# Esquematico.net
KiCad netlist of a schematic drawn in EAGLE
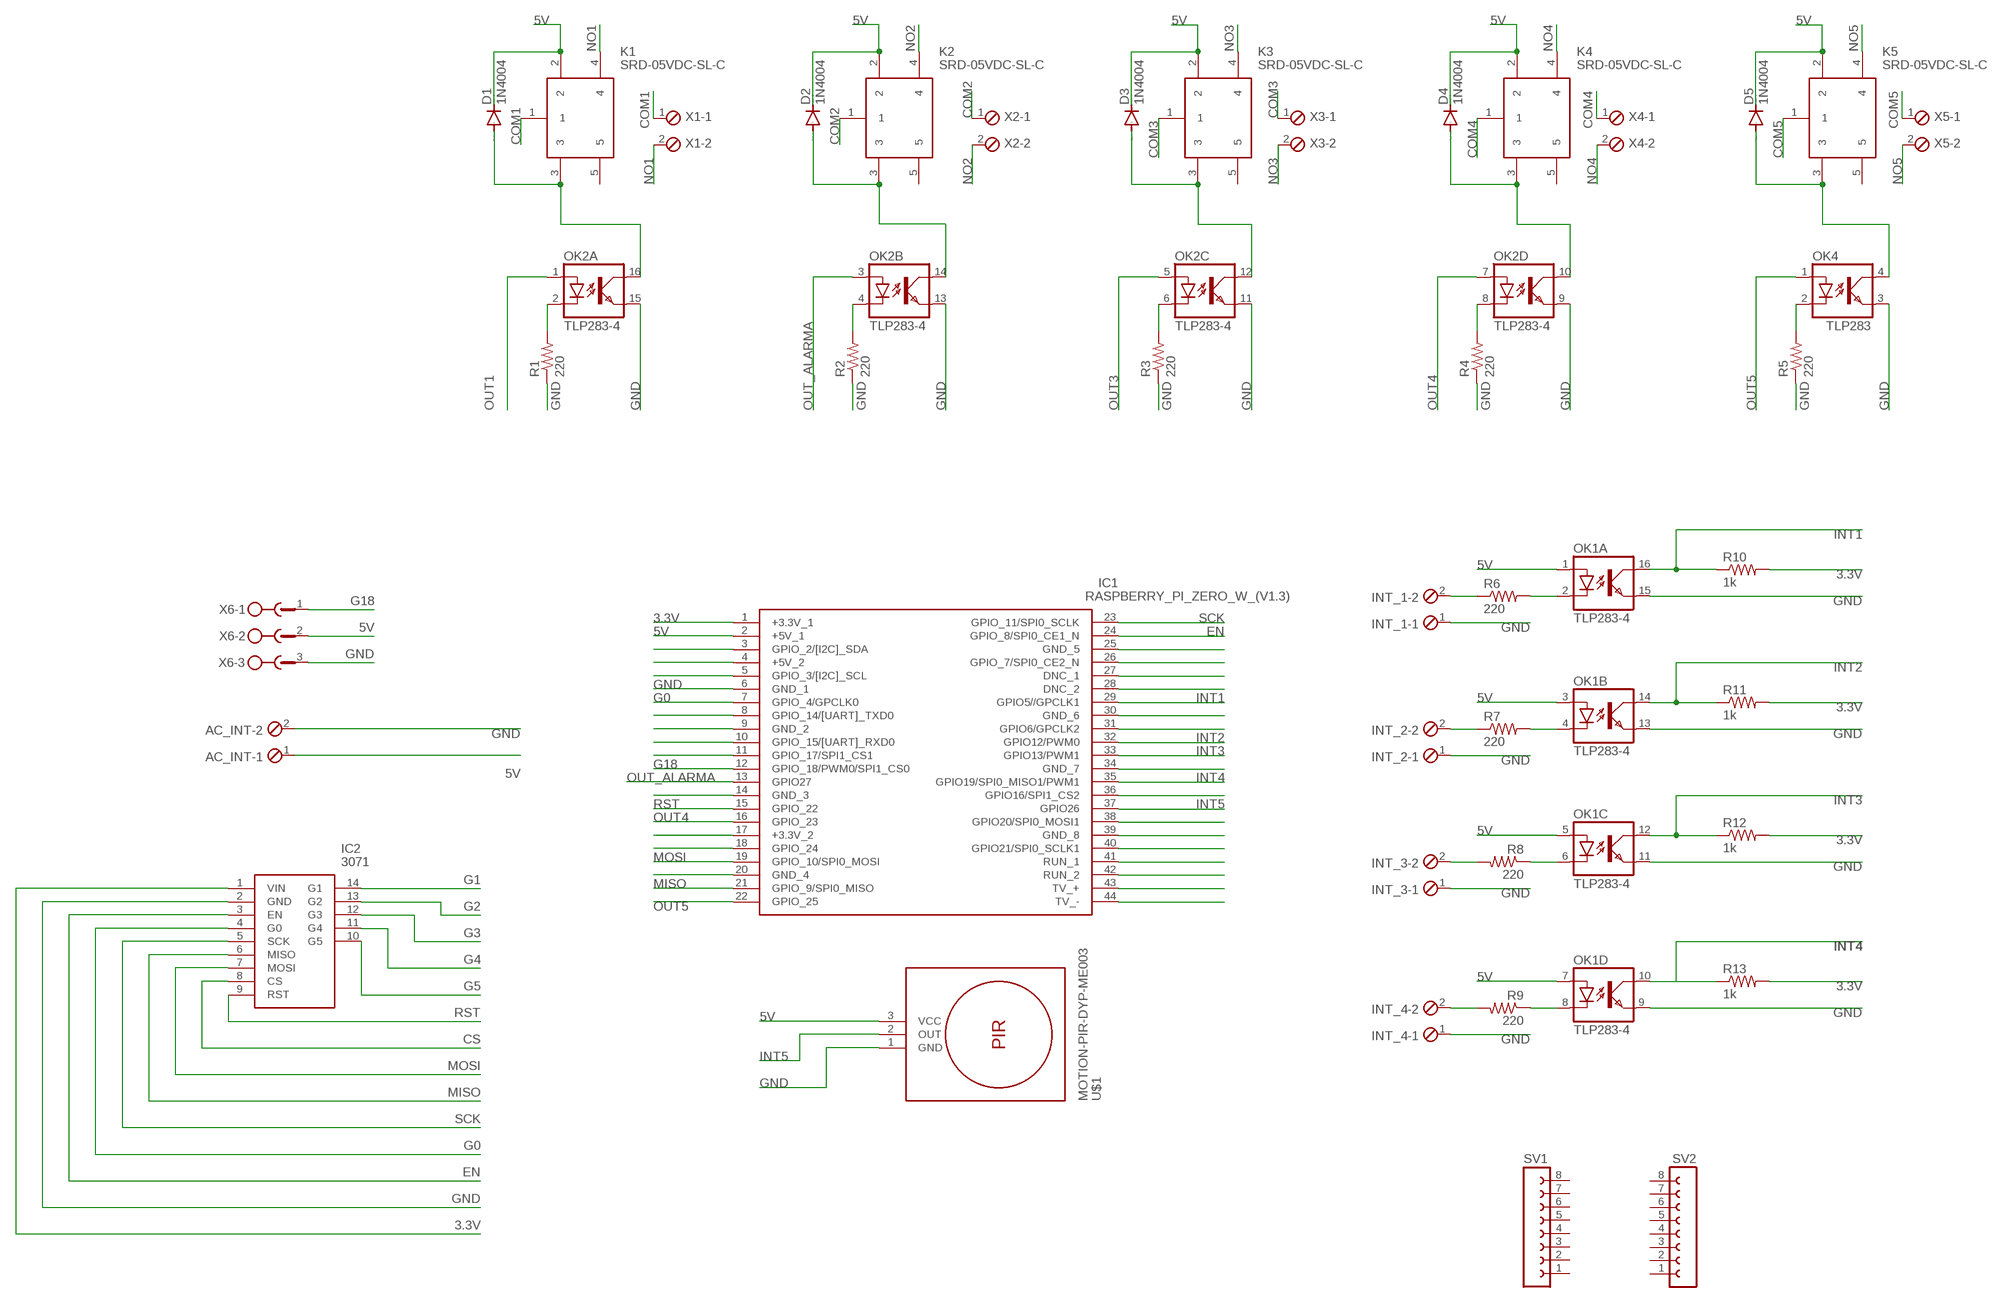
[diagram p0: schematic, sheet 1]

(export (version "E")
  (design (tool "Eeschema 10.0.6"))
  (components
    (comp (ref "AC_INT")
      (value "MPT2")
      (footprint "eagle-import:2POL254")
      (libsource (lib "eagle-import") (part "MPT2"))
    )
    (comp (ref "D1")
      (value "1N4004")
      (footprint "eagle-import:DO41-10")
      (libsource (lib "eagle-import") (part "1N4004"))
    )
    (comp (ref "D2")
      (value "1N4004")
      (footprint "eagle-import:DO41-10")
      (libsource (lib "eagle-import") (part "1N4004"))
    )
    (comp (ref "D3")
      (value "1N4004")
      (footprint "eagle-import:DO41-10")
      (libsource (lib "eagle-import") (part "1N4004"))
    )
    (comp (ref "D4")
      (value "1N4004")
      (footprint "eagle-import:DO41-10")
      (libsource (lib "eagle-import") (part "1N4004"))
    )
    (comp (ref "D5")
      (value "1N4004")
      (footprint "eagle-import:DO41-10")
      (libsource (lib "eagle-import") (part "1N4004"))
    )
    (comp (ref "IC1")
      (value "RASPBERRY_PI_ZERO_W_(V1.3)")
      (footprint "eagle-import:RASPBERRYPIZEROWV13")
      (fields (field (name "MANUFACTURER_PART_NUMBER") "Raspberry Pi Zero W (v1.3)"))
      (libsource (lib "eagle-import") (part "RASPBERRY_PI_ZERO_W_(V1.3)"))
    )
    (comp (ref "IC2")
      (value "3071")
      (footprint "eagle-import:3071")
      (fields (field (name "MOUSER_PART_NUMBER") "485-3071"))
      (libsource (lib "eagle-import") (part "3071"))
    )
    (comp (ref "INT_1")
      (value "MPT2")
      (footprint "eagle-import:2POL254")
      (libsource (lib "eagle-import") (part "MPT2"))
    )
    (comp (ref "INT_2")
      (value "MPT2")
      (footprint "eagle-import:2POL254")
      (libsource (lib "eagle-import") (part "MPT2"))
    )
    (comp (ref "INT_3")
      (value "MPT2")
      (footprint "eagle-import:2POL254")
      (libsource (lib "eagle-import") (part "MPT2"))
    )
    (comp (ref "INT_4")
      (value "MPT2")
      (footprint "eagle-import:2POL254")
      (libsource (lib "eagle-import") (part "MPT2"))
    )
    (comp (ref "K1")
      (value "SRD-05VDC-SL-C")
      (footprint "eagle-import:SRD")
      (libsource (lib "eagle-import") (part "SRD-05VDC-SL-C"))
    )
    (comp (ref "K2")
      (value "SRD-05VDC-SL-C")
      (footprint "eagle-import:SRD")
      (libsource (lib "eagle-import") (part "SRD-05VDC-SL-C"))
    )
    (comp (ref "K3")
      (value "SRD-05VDC-SL-C")
      (footprint "eagle-import:SRD")
      (libsource (lib "eagle-import") (part "SRD-05VDC-SL-C"))
    )
    (comp (ref "K4")
      (value "SRD-05VDC-SL-C")
      (footprint "eagle-import:SRD")
      (libsource (lib "eagle-import") (part "SRD-05VDC-SL-C"))
    )
    (comp (ref "K5")
      (value "SRD-05VDC-SL-C")
      (footprint "eagle-import:SRD")
      (libsource (lib "eagle-import") (part "SRD-05VDC-SL-C"))
    )
    (comp (ref "OK1")
      (value "TLP283-4")
      (footprint "eagle-import:MINI-FLAT-16")
      (libsource (lib "eagle-import") (part "TLP283-4"))
    )
    (comp (ref "OK2")
      (value "TLP283-4")
      (footprint "eagle-import:MINI-FLAT-16")
      (libsource (lib "eagle-import") (part "TLP283-4"))
    )
    (comp (ref "OK4")
      (value "TLP283")
      (footprint "eagle-import:MINI-FLAT-4")
      (libsource (lib "eagle-import") (part "TLP283"))
    )
    (comp (ref "R1")
      (value "220")
      (footprint "eagle-import:R0402")
      (libsource (lib "eagle-import") (part "R-US_R0402"))
    )
    (comp (ref "R2")
      (value "220")
      (footprint "eagle-import:R0402")
      (libsource (lib "eagle-import") (part "R-US_R0402"))
    )
    (comp (ref "R3")
      (value "220")
      (footprint "eagle-import:R0402")
      (libsource (lib "eagle-import") (part "R-US_R0402"))
    )
    (comp (ref "R4")
      (value "220")
      (footprint "eagle-import:R0402")
      (libsource (lib "eagle-import") (part "R-US_R0402"))
    )
    (comp (ref "R5")
      (value "220")
      (footprint "eagle-import:R0402")
      (libsource (lib "eagle-import") (part "R-US_R0402"))
    )
    (comp (ref "R6")
      (value "220")
      (footprint "eagle-import:R0402")
      (libsource (lib "eagle-import") (part "R-US_R0402"))
    )
    (comp (ref "R7")
      (value "220")
      (footprint "eagle-import:R0402")
      (libsource (lib "eagle-import") (part "R-US_R0402"))
    )
    (comp (ref "R8")
      (value "220")
      (footprint "eagle-import:R0402")
      (libsource (lib "eagle-import") (part "R-US_R0402"))
    )
    (comp (ref "R9")
      (value "220")
      (footprint "eagle-import:R0402")
      (libsource (lib "eagle-import") (part "R-US_R0402"))
    )
    (comp (ref "R10")
      (value "1k")
      (footprint "eagle-import:R0402")
      (libsource (lib "eagle-import") (part "R-US_R0402"))
    )
    (comp (ref "R11")
      (value "1k")
      (footprint "eagle-import:R0402")
      (libsource (lib "eagle-import") (part "R-US_R0402"))
    )
    (comp (ref "R12")
      (value "1k")
      (footprint "eagle-import:R0402")
      (libsource (lib "eagle-import") (part "R-US_R0402"))
    )
    (comp (ref "R13")
      (value "1k")
      (footprint "eagle-import:R0402")
      (libsource (lib "eagle-import") (part "R-US_R0402"))
    )
    (comp (ref "SV1")
      (value "FE08W")
      (footprint "eagle-import:FE08W")
      (libsource (lib "eagle-import") (part "FE08W"))
    )
    (comp (ref "SV2")
      (value "FE08W")
      (footprint "eagle-import:FE08W")
      (libsource (lib "eagle-import") (part "FE08W"))
    )
    (comp (ref "U$1")
      (value "MOTION-PIR-DYP-ME003")
      (footprint "eagle-import:MOTION-PIR-DYP-ME003")
      (libsource (lib "eagle-import") (part "MOTION-PIR-DYP-ME003"))
    )
    (comp (ref "X1")
      (value "MPT2")
      (footprint "eagle-import:2POL254")
      (libsource (lib "eagle-import") (part "MPT2"))
    )
    (comp (ref "X2")
      (value "MPT2")
      (footprint "eagle-import:2POL254")
      (libsource (lib "eagle-import") (part "MPT2"))
    )
    (comp (ref "X3")
      (value "MPT2")
      (footprint "eagle-import:2POL254")
      (libsource (lib "eagle-import") (part "MPT2"))
    )
    (comp (ref "X4")
      (value "MPT2")
      (footprint "eagle-import:2POL254")
      (libsource (lib "eagle-import") (part "MPT2"))
    )
    (comp (ref "X5")
      (value "MPT2")
      (footprint "eagle-import:2POL254")
      (libsource (lib "eagle-import") (part "MPT2"))
    )
    (comp (ref "X6")
      (value "W232-3")
      (footprint "eagle-import:W232-3")
      (libsource (lib "eagle-import") (part "W232-3"))
    )
  )
  (nets
    (net (code "1") (name "/3.3V") (class "Default")
      (node (ref "IC1") (pin "1") (pinfunction "+3.3V_1_1") (pintype "bidirectional"))
      (node (ref "IC2") (pin "1") (pinfunction "VIN_1") (pintype "bidirectional"))
      (node (ref "R10") (pin "2") (pinfunction "2_2") (pintype "passive"))
      (node (ref "R11") (pin "2") (pinfunction "2_2") (pintype "passive"))
      (node (ref "R12") (pin "2") (pinfunction "2_2") (pintype "passive"))
      (node (ref "R13") (pin "2") (pinfunction "2_2") (pintype "passive"))
    )
    (net (code "2") (name "/5V") (class "Default")
      (node (ref "AC_INT") (pin "1") (pinfunction "1_1") (pintype "passive"))
      (node (ref "D1") (pin "C") (pinfunction "C_C") (pintype "passive"))
      (node (ref "D2") (pin "C") (pinfunction "C_C") (pintype "passive"))
      (node (ref "D3") (pin "C") (pinfunction "C_C") (pintype "passive"))
      (node (ref "D4") (pin "C") (pinfunction "C_C") (pintype "passive"))
      (node (ref "D5") (pin "C") (pinfunction "C_C") (pintype "passive"))
      (node (ref "IC1") (pin "2") (pinfunction "+5V_1_2") (pintype "bidirectional"))
      (node (ref "K1") (pin "2") (pinfunction "2_2") (pintype "bidirectional"))
      (node (ref "K2") (pin "2") (pinfunction "2_2") (pintype "bidirectional"))
      (node (ref "K3") (pin "2") (pinfunction "2_2") (pintype "bidirectional"))
      (node (ref "K4") (pin "2") (pinfunction "2_2") (pintype "bidirectional"))
      (node (ref "K5") (pin "2") (pinfunction "2_2") (pintype "bidirectional"))
      (node (ref "OK1") (pin "1") (pinfunction "A_1") (pintype "passive"))
      (node (ref "OK1") (pin "3") (pinfunction "A_3") (pintype "passive"))
      (node (ref "OK1") (pin "5") (pinfunction "A_5") (pintype "passive"))
      (node (ref "OK1") (pin "7") (pinfunction "A_7") (pintype "passive"))
      (node (ref "U$1") (pin "3") (pinfunction "VCC_3") (pintype "power_in"))
      (node (ref "X6") (pin "2") (pinfunction "SK_2") (pintype "passive"))
    )
    (net (code "3") (name "/COM1") (class "Default")
      (node (ref "K1") (pin "1") (pinfunction "1_1") (pintype "bidirectional"))
      (node (ref "X1") (pin "1") (pinfunction "1_1") (pintype "passive"))
    )
    (net (code "4") (name "/COM2") (class "Default")
      (node (ref "K2") (pin "1") (pinfunction "1_1") (pintype "bidirectional"))
      (node (ref "X2") (pin "1") (pinfunction "1_1") (pintype "passive"))
    )
    (net (code "5") (name "/COM3") (class "Default")
      (node (ref "K3") (pin "1") (pinfunction "1_1") (pintype "bidirectional"))
      (node (ref "X3") (pin "1") (pinfunction "1_1") (pintype "passive"))
    )
    (net (code "6") (name "/COM4") (class "Default")
      (node (ref "K4") (pin "1") (pinfunction "1_1") (pintype "bidirectional"))
      (node (ref "X4") (pin "1") (pinfunction "1_1") (pintype "passive"))
    )
    (net (code "7") (name "/COM5") (class "Default")
      (node (ref "K5") (pin "1") (pinfunction "1_1") (pintype "bidirectional"))
      (node (ref "X5") (pin "1") (pinfunction "1_1") (pintype "passive"))
    )
    (net (code "8") (name "/CS") (class "Default")
      (node (ref "IC2") (pin "8") (pinfunction "CS_8") (pintype "bidirectional"))
    )
    (net (code "9") (name "/EN") (class "Default")
      (node (ref "IC1") (pin "24") (pinfunction "GPIO_8/SPI0_CE1_N_24") (pintype "bidirectional"))
      (node (ref "IC2") (pin "3") (pinfunction "EN_3") (pintype "bidirectional"))
    )
    (net (code "10") (name "/G0") (class "Default")
      (node (ref "IC1") (pin "7") (pinfunction "GPIO_4/GPCLK0_7") (pintype "bidirectional"))
      (node (ref "IC2") (pin "4") (pinfunction "G0_4") (pintype "bidirectional"))
    )
    (net (code "11") (name "/G1") (class "Default")
      (node (ref "IC2") (pin "14") (pinfunction "G1_14") (pintype "bidirectional"))
    )
    (net (code "12") (name "/G2") (class "Default")
      (node (ref "IC2") (pin "13") (pinfunction "G2_13") (pintype "bidirectional"))
    )
    (net (code "13") (name "/G3") (class "Default")
      (node (ref "IC2") (pin "12") (pinfunction "G3_12") (pintype "bidirectional"))
    )
    (net (code "14") (name "/G4") (class "Default")
      (node (ref "IC2") (pin "11") (pinfunction "G4_11") (pintype "bidirectional"))
    )
    (net (code "15") (name "/G5") (class "Default")
      (node (ref "IC2") (pin "10") (pinfunction "G5_10") (pintype "bidirectional"))
    )
    (net (code "16") (name "/G18") (class "Default")
      (node (ref "IC1") (pin "12") (pinfunction "GPIO_18/PWM0/SPI1_CS0_12") (pintype "bidirectional"))
      (node (ref "X6") (pin "1") (pinfunction "SK_1") (pintype "passive"))
    )
    (net (code "17") (name "/GND") (class "Default")
      (node (ref "AC_INT") (pin "2") (pinfunction "1_2") (pintype "passive"))
      (node (ref "IC1") (pin "6") (pinfunction "GND_1_6") (pintype "bidirectional"))
      (node (ref "IC2") (pin "2") (pinfunction "GND_2") (pintype "bidirectional"))
      (node (ref "INT_1") (pin "1") (pinfunction "1_1") (pintype "passive"))
      (node (ref "INT_2") (pin "1") (pinfunction "1_1") (pintype "passive"))
      (node (ref "INT_3") (pin "1") (pinfunction "1_1") (pintype "passive"))
      (node (ref "INT_4") (pin "1") (pinfunction "1_1") (pintype "passive"))
      (node (ref "OK1") (pin "11") (pinfunction "EMIT_11") (pintype "passive"))
      (node (ref "OK1") (pin "13") (pinfunction "EMIT_13") (pintype "passive"))
      (node (ref "OK1") (pin "15") (pinfunction "EMIT_15") (pintype "passive"))
      (node (ref "OK1") (pin "9") (pinfunction "EMIT_9") (pintype "passive"))
      (node (ref "OK2") (pin "11") (pinfunction "EMIT_11") (pintype "passive"))
      (node (ref "OK2") (pin "13") (pinfunction "EMIT_13") (pintype "passive"))
      (node (ref "OK2") (pin "15") (pinfunction "EMIT_15") (pintype "passive"))
      (node (ref "OK2") (pin "9") (pinfunction "EMIT_9") (pintype "passive"))
      (node (ref "OK4") (pin "3") (pinfunction "EMIT_3") (pintype "passive"))
      (node (ref "R1") (pin "1") (pinfunction "1_1") (pintype "passive"))
      (node (ref "R2") (pin "1") (pinfunction "1_1") (pintype "passive"))
      (node (ref "R3") (pin "1") (pinfunction "1_1") (pintype "passive"))
      (node (ref "R4") (pin "1") (pinfunction "1_1") (pintype "passive"))
      (node (ref "R5") (pin "1") (pinfunction "1_1") (pintype "passive"))
      (node (ref "U$1") (pin "1") (pinfunction "GND_1") (pintype "power_in"))
      (node (ref "X6") (pin "3") (pinfunction "SK_3") (pintype "passive"))
    )
    (net (code "18") (name "/INT1") (class "Default")
      (node (ref "IC1") (pin "29") (pinfunction "GPIO5//GPCLK1_29") (pintype "bidirectional"))
      (node (ref "OK1") (pin "16") (pinfunction "COL_16") (pintype "passive"))
      (node (ref "R10") (pin "1") (pinfunction "1_1") (pintype "passive"))
    )
    (net (code "19") (name "/INT2") (class "Default")
      (node (ref "IC1") (pin "32") (pinfunction "GPIO12/PWM0_32") (pintype "bidirectional"))
      (node (ref "OK1") (pin "14") (pinfunction "COL_14") (pintype "passive"))
      (node (ref "R11") (pin "1") (pinfunction "1_1") (pintype "passive"))
    )
    (net (code "20") (name "/INT3") (class "Default")
      (node (ref "IC1") (pin "33") (pinfunction "GPIO13/PWM1_33") (pintype "bidirectional"))
      (node (ref "OK1") (pin "12") (pinfunction "COL_12") (pintype "passive"))
      (node (ref "R12") (pin "1") (pinfunction "1_1") (pintype "passive"))
    )
    (net (code "21") (name "/INT4") (class "Default")
      (node (ref "IC1") (pin "35") (pinfunction "GPIO19/SPI0_MISO1/PWM1_35") (pintype "bidirectional"))
      (node (ref "OK1") (pin "10") (pinfunction "COL_10") (pintype "passive"))
      (node (ref "R13") (pin "1") (pinfunction "1_1") (pintype "passive"))
    )
    (net (code "22") (name "/INT5") (class "Default")
      (node (ref "IC1") (pin "37") (pinfunction "GPIO26_37") (pintype "bidirectional"))
      (node (ref "U$1") (pin "2") (pinfunction "OUT_2") (pintype "output"))
    )
    (net (code "23") (name "/MISO") (class "Default")
      (node (ref "IC1") (pin "21") (pinfunction "GPIO_9/SPI0_MISO_21") (pintype "bidirectional"))
      (node (ref "IC2") (pin "6") (pinfunction "MISO_6") (pintype "bidirectional"))
    )
    (net (code "24") (name "/MOSI") (class "Default")
      (node (ref "IC1") (pin "19") (pinfunction "GPIO_10/SPI0_MOSI_19") (pintype "bidirectional"))
      (node (ref "IC2") (pin "7") (pinfunction "MOSI_7") (pintype "bidirectional"))
    )
    (net (code "25") (name "/NO1") (class "Default")
      (node (ref "K1") (pin "4") (pinfunction "4_4") (pintype "bidirectional"))
      (node (ref "X1") (pin "2") (pinfunction "1_2") (pintype "passive"))
    )
    (net (code "26") (name "/NO2") (class "Default")
      (node (ref "K2") (pin "4") (pinfunction "4_4") (pintype "bidirectional"))
      (node (ref "X2") (pin "2") (pinfunction "1_2") (pintype "passive"))
    )
    (net (code "27") (name "/NO3") (class "Default")
      (node (ref "K3") (pin "4") (pinfunction "4_4") (pintype "bidirectional"))
      (node (ref "X3") (pin "2") (pinfunction "1_2") (pintype "passive"))
    )
    (net (code "28") (name "/NO4") (class "Default")
      (node (ref "K4") (pin "4") (pinfunction "4_4") (pintype "bidirectional"))
      (node (ref "X4") (pin "2") (pinfunction "1_2") (pintype "passive"))
    )
    (net (code "29") (name "/NO5") (class "Default")
      (node (ref "K5") (pin "4") (pinfunction "4_4") (pintype "bidirectional"))
      (node (ref "X5") (pin "2") (pinfunction "1_2") (pintype "passive"))
    )
    (net (code "30") (name "/OUT1") (class "Default")
      (node (ref "OK2") (pin "1") (pinfunction "A_1") (pintype "passive"))
    )
    (net (code "31") (name "/OUT3") (class "Default")
      (node (ref "OK2") (pin "5") (pinfunction "A_5") (pintype "passive"))
    )
    (net (code "32") (name "/OUT4") (class "Default")
      (node (ref "IC1") (pin "16") (pinfunction "GPIO_23_16") (pintype "bidirectional"))
      (node (ref "OK2") (pin "7") (pinfunction "A_7") (pintype "passive"))
    )
    (net (code "33") (name "/OUT5") (class "Default")
      (node (ref "IC1") (pin "22") (pinfunction "GPIO_25_22") (pintype "bidirectional"))
      (node (ref "OK4") (pin "1") (pinfunction "A_1") (pintype "passive"))
    )
    (net (code "34") (name "/OUT_ALARMA") (class "Default")
      (node (ref "IC1") (pin "13") (pinfunction "GPIO27_13") (pintype "bidirectional"))
      (node (ref "OK2") (pin "3") (pinfunction "A_3") (pintype "passive"))
    )
    (net (code "35") (name "/RST") (class "Default")
      (node (ref "IC1") (pin "15") (pinfunction "GPIO_22_15") (pintype "bidirectional"))
      (node (ref "IC2") (pin "9") (pinfunction "RST_9") (pintype "bidirectional"))
    )
    (net (code "36") (name "/SCK") (class "Default")
      (node (ref "IC1") (pin "23") (pinfunction "GPIO_11/SPI0_SCLK_23") (pintype "bidirectional"))
      (node (ref "IC2") (pin "5") (pinfunction "SCK_5") (pintype "bidirectional"))
    )
    (net (code "37") (name "Net-(INT_1B-1)") (class "Default")
      (node (ref "INT_1") (pin "2") (pinfunction "1_2") (pintype "passive"))
      (node (ref "R6") (pin "1") (pinfunction "1_1") (pintype "passive"))
    )
    (net (code "38") (name "Net-(INT_2B-1)") (class "Default")
      (node (ref "INT_2") (pin "2") (pinfunction "1_2") (pintype "passive"))
      (node (ref "R7") (pin "1") (pinfunction "1_1") (pintype "passive"))
    )
    (net (code "39") (name "Net-(INT_3B-1)") (class "Default")
      (node (ref "INT_3") (pin "2") (pinfunction "1_2") (pintype "passive"))
      (node (ref "R8") (pin "2") (pinfunction "2_2") (pintype "passive"))
    )
    (net (code "40") (name "Net-(INT_4B-1)") (class "Default")
      (node (ref "INT_4") (pin "2") (pinfunction "1_2") (pintype "passive"))
      (node (ref "R9") (pin "2") (pinfunction "2_2") (pintype "passive"))
    )
    (net (code "41") (name "Net-(OK1A-C)") (class "Default")
      (node (ref "OK1") (pin "2") (pinfunction "C_2") (pintype "passive"))
      (node (ref "R6") (pin "2") (pinfunction "2_2") (pintype "passive"))
    )
    (net (code "42") (name "Net-(OK1B-C)") (class "Default")
      (node (ref "OK1") (pin "4") (pinfunction "C_4") (pintype "passive"))
      (node (ref "R7") (pin "2") (pinfunction "2_2") (pintype "passive"))
    )
    (net (code "43") (name "Net-(OK1C-C)") (class "Default")
      (node (ref "OK1") (pin "6") (pinfunction "C_6") (pintype "passive"))
      (node (ref "R8") (pin "1") (pinfunction "1_1") (pintype "passive"))
    )
    (net (code "44") (name "Net-(OK1D-C)") (class "Default")
      (node (ref "OK1") (pin "8") (pinfunction "C_8") (pintype "passive"))
      (node (ref "R9") (pin "1") (pinfunction "1_1") (pintype "passive"))
    )
    (net (code "45") (name "Net-(OK2A-C)") (class "Default")
      (node (ref "OK2") (pin "2") (pinfunction "C_2") (pintype "passive"))
      (node (ref "R1") (pin "2") (pinfunction "2_2") (pintype "passive"))
    )
    (net (code "46") (name "Net-(OK2A-COL)") (class "Default")
      (node (ref "D1") (pin "A") (pinfunction "A_A") (pintype "passive"))
      (node (ref "K1") (pin "3") (pinfunction "3_3") (pintype "bidirectional"))
      (node (ref "OK2") (pin "16") (pinfunction "COL_16") (pintype "passive"))
    )
    (net (code "47") (name "Net-(OK2B-C)") (class "Default")
      (node (ref "OK2") (pin "4") (pinfunction "C_4") (pintype "passive"))
      (node (ref "R2") (pin "2") (pinfunction "2_2") (pintype "passive"))
    )
    (net (code "48") (name "Net-(OK2B-COL)") (class "Default")
      (node (ref "D2") (pin "A") (pinfunction "A_A") (pintype "passive"))
      (node (ref "K2") (pin "3") (pinfunction "3_3") (pintype "bidirectional"))
      (node (ref "OK2") (pin "14") (pinfunction "COL_14") (pintype "passive"))
    )
    (net (code "49") (name "Net-(OK2C-C)") (class "Default")
      (node (ref "OK2") (pin "6") (pinfunction "C_6") (pintype "passive"))
      (node (ref "R3") (pin "2") (pinfunction "2_2") (pintype "passive"))
    )
    (net (code "50") (name "Net-(OK2C-COL)") (class "Default")
      (node (ref "D3") (pin "A") (pinfunction "A_A") (pintype "passive"))
      (node (ref "K3") (pin "3") (pinfunction "3_3") (pintype "bidirectional"))
      (node (ref "OK2") (pin "12") (pinfunction "COL_12") (pintype "passive"))
    )
    (net (code "51") (name "Net-(OK2D-C)") (class "Default")
      (node (ref "OK2") (pin "8") (pinfunction "C_8") (pintype "passive"))
      (node (ref "R4") (pin "2") (pinfunction "2_2") (pintype "passive"))
    )
    (net (code "52") (name "Net-(OK2D-COL)") (class "Default")
      (node (ref "D4") (pin "A") (pinfunction "A_A") (pintype "passive"))
      (node (ref "K4") (pin "3") (pinfunction "3_3") (pintype "bidirectional"))
      (node (ref "OK2") (pin "10") (pinfunction "COL_10") (pintype "passive"))
    )
    (net (code "53") (name "Net-(OK4-C)") (class "Default")
      (node (ref "OK4") (pin "2") (pinfunction "C_2") (pintype "passive"))
      (node (ref "R5") (pin "2") (pinfunction "2_2") (pintype "passive"))
    )
    (net (code "54") (name "Net-(OK4-COL)") (class "Default")
      (node (ref "D5") (pin "A") (pinfunction "A_A") (pintype "passive"))
      (node (ref "K5") (pin "3") (pinfunction "3_3") (pintype "bidirectional"))
      (node (ref "OK4") (pin "4") (pinfunction "COL_4") (pintype "passive"))
    )
    (net (code "55") (name "unconnected-(IC1-+3.3V_2-Pad17)") (class "Default")
      (node (ref "IC1") (pin "17") (pinfunction "+3.3V_2_17") (pintype "bidirectional"))
    )
    (net (code "56") (name "unconnected-(IC1-+5V_2-Pad4)") (class "Default")
      (node (ref "IC1") (pin "4") (pinfunction "+5V_2_4") (pintype "bidirectional"))
    )
    (net (code "57") (name "unconnected-(IC1-DNC_1-Pad27)") (class "Default")
      (node (ref "IC1") (pin "27") (pinfunction "DNC_1_27") (pintype "bidirectional"))
    )
    (net (code "58") (name "unconnected-(IC1-DNC_2-Pad28)") (class "Default")
      (node (ref "IC1") (pin "28") (pinfunction "DNC_2_28") (pintype "bidirectional"))
    )
    (net (code "59") (name "unconnected-(IC1-GND_2-Pad9)") (class "Default")
      (node (ref "IC1") (pin "9") (pinfunction "GND_2_9") (pintype "bidirectional"))
    )
    (net (code "60") (name "unconnected-(IC1-GND_3-Pad14)") (class "Default")
      (node (ref "IC1") (pin "14") (pinfunction "GND_3_14") (pintype "bidirectional"))
    )
    (net (code "61") (name "unconnected-(IC1-GND_4-Pad20)") (class "Default")
      (node (ref "IC1") (pin "20") (pinfunction "GND_4_20") (pintype "bidirectional"))
    )
    (net (code "62") (name "unconnected-(IC1-GND_5-Pad25)") (class "Default")
      (node (ref "IC1") (pin "25") (pinfunction "GND_5_25") (pintype "bidirectional"))
    )
    (net (code "63") (name "unconnected-(IC1-GND_6-Pad30)") (class "Default")
      (node (ref "IC1") (pin "30") (pinfunction "GND_6_30") (pintype "bidirectional"))
    )
    (net (code "64") (name "unconnected-(IC1-GND_7-Pad34)") (class "Default")
      (node (ref "IC1") (pin "34") (pinfunction "GND_7_34") (pintype "bidirectional"))
    )
    (net (code "65") (name "unconnected-(IC1-GND_8-Pad39)") (class "Default")
      (node (ref "IC1") (pin "39") (pinfunction "GND_8_39") (pintype "bidirectional"))
    )
    (net (code "66") (name "unconnected-(IC1-GPIO6{slash}GPCLK2-Pad31)") (class "Default")
      (node (ref "IC1") (pin "31") (pinfunction "GPIO6/GPCLK2_31") (pintype "bidirectional"))
    )
    (net (code "67") (name "unconnected-(IC1-GPIO16{slash}SPI1_CS2-Pad36)") (class "Default")
      (node (ref "IC1") (pin "36") (pinfunction "GPIO16/SPI1_CS2_36") (pintype "bidirectional"))
    )
    (net (code "68") (name "unconnected-(IC1-GPIO20{slash}SPI0_MOSI1-Pad38)") (class "Default")
      (node (ref "IC1") (pin "38") (pinfunction "GPIO20/SPI0_MOSI1_38") (pintype "bidirectional"))
    )
    (net (code "69") (name "unconnected-(IC1-GPIO21{slash}SPI0_SCLK1-Pad40)") (class "Default")
      (node (ref "IC1") (pin "40") (pinfunction "GPIO21/SPI0_SCLK1_40") (pintype "bidirectional"))
    )
    (net (code "70") (name "unconnected-(IC1-GPIO_2{slash}[I2C]_SDA-Pad3)") (class "Default")
      (node (ref "IC1") (pin "3") (pinfunction "GPIO_2/[I2C]_SDA_3") (pintype "bidirectional"))
    )
    (net (code "71") (name "unconnected-(IC1-GPIO_3{slash}[I2C]_SCL-Pad5)") (class "Default")
      (node (ref "IC1") (pin "5") (pinfunction "GPIO_3/[I2C]_SCL_5") (pintype "bidirectional"))
    )
    (net (code "72") (name "unconnected-(IC1-GPIO_7{slash}SPI0_CE2_N-Pad26)") (class "Default")
      (node (ref "IC1") (pin "26") (pinfunction "GPIO_7/SPI0_CE2_N_26") (pintype "bidirectional"))
    )
    (net (code "73") (name "unconnected-(IC1-GPIO_14{slash}[UART]_TXD0-Pad8)") (class "Default")
      (node (ref "IC1") (pin "8") (pinfunction "GPIO_14/[UART]_TXD0_8") (pintype "bidirectional"))
    )
    (net (code "74") (name "unconnected-(IC1-GPIO_15{slash}[UART]_RXD0-Pad10)") (class "Default")
      (node (ref "IC1") (pin "10") (pinfunction "GPIO_15/[UART]_RXD0_10") (pintype "bidirectional"))
    )
    (net (code "75") (name "unconnected-(IC1-GPIO_17{slash}SPI1_CS1-Pad11)") (class "Default")
      (node (ref "IC1") (pin "11") (pinfunction "GPIO_17/SPI1_CS1_11") (pintype "bidirectional"))
    )
    (net (code "76") (name "unconnected-(IC1-GPIO_24-Pad18)") (class "Default")
      (node (ref "IC1") (pin "18") (pinfunction "GPIO_24_18") (pintype "bidirectional"))
    )
    (net (code "77") (name "unconnected-(IC1-RUN_1-Pad41)") (class "Default")
      (node (ref "IC1") (pin "41") (pinfunction "RUN_1_41") (pintype "bidirectional"))
    )
    (net (code "78") (name "unconnected-(IC1-RUN_2-Pad42)") (class "Default")
      (node (ref "IC1") (pin "42") (pinfunction "RUN_2_42") (pintype "bidirectional"))
    )
    (net (code "79") (name "unconnected-(IC1-TV_+-Pad43)") (class "Default")
      (node (ref "IC1") (pin "43") (pinfunction "TV_+_43") (pintype "bidirectional"))
    )
    (net (code "80") (name "unconnected-(IC1-TV_--Pad44)") (class "Default")
      (node (ref "IC1") (pin "44") (pinfunction "TV_-_44") (pintype "bidirectional"))
    )
    (net (code "81") (name "unconnected-(K1-Pad5)") (class "Default")
      (node (ref "K1") (pin "5") (pinfunction "5_5") (pintype "bidirectional"))
    )
    (net (code "82") (name "unconnected-(K2-Pad5)") (class "Default")
      (node (ref "K2") (pin "5") (pinfunction "5_5") (pintype "bidirectional"))
    )
    (net (code "83") (name "unconnected-(K3-Pad5)") (class "Default")
      (node (ref "K3") (pin "5") (pinfunction "5_5") (pintype "bidirectional"))
    )
    (net (code "84") (name "unconnected-(K4-Pad5)") (class "Default")
      (node (ref "K4") (pin "5") (pinfunction "5_5") (pintype "bidirectional"))
    )
    (net (code "85") (name "unconnected-(K5-Pad5)") (class "Default")
      (node (ref "K5") (pin "5") (pinfunction "5_5") (pintype "bidirectional"))
    )
    (net (code "86") (name "unconnected-(SV1-Pad1)") (class "Default")
      (node (ref "SV1") (pin "1") (pinfunction "1_1") (pintype "passive"))
    )
    (net (code "87") (name "unconnected-(SV1-Pad2)") (class "Default")
      (node (ref "SV1") (pin "2") (pinfunction "2_2") (pintype "passive"))
    )
    (net (code "88") (name "unconnected-(SV1-Pad3)") (class "Default")
      (node (ref "SV1") (pin "3") (pinfunction "3_3") (pintype "passive"))
    )
    (net (code "89") (name "unconnected-(SV1-Pad4)") (class "Default")
      (node (ref "SV1") (pin "4") (pinfunction "4_4") (pintype "passive"))
    )
    (net (code "90") (name "unconnected-(SV1-Pad5)") (class "Default")
      (node (ref "SV1") (pin "5") (pinfunction "5_5") (pintype "passive"))
    )
    (net (code "91") (name "unconnected-(SV1-Pad6)") (class "Default")
      (node (ref "SV1") (pin "6") (pinfunction "6_6") (pintype "passive"))
    )
    (net (code "92") (name "unconnected-(SV1-Pad7)") (class "Default")
      (node (ref "SV1") (pin "7") (pinfunction "7_7") (pintype "passive"))
    )
    (net (code "93") (name "unconnected-(SV1-Pad8)") (class "Default")
      (node (ref "SV1") (pin "8") (pinfunction "8_8") (pintype "passive"))
    )
    (net (code "94") (name "unconnected-(SV2-Pad1)") (class "Default")
      (node (ref "SV2") (pin "1") (pinfunction "1_1") (pintype "passive"))
    )
    (net (code "95") (name "unconnected-(SV2-Pad2)") (class "Default")
      (node (ref "SV2") (pin "2") (pinfunction "2_2") (pintype "passive"))
    )
    (net (code "96") (name "unconnected-(SV2-Pad3)") (class "Default")
      (node (ref "SV2") (pin "3") (pinfunction "3_3") (pintype "passive"))
    )
    (net (code "97") (name "unconnected-(SV2-Pad4)") (class "Default")
      (node (ref "SV2") (pin "4") (pinfunction "4_4") (pintype "passive"))
    )
    (net (code "98") (name "unconnected-(SV2-Pad5)") (class "Default")
      (node (ref "SV2") (pin "5") (pinfunction "5_5") (pintype "passive"))
    )
    (net (code "99") (name "unconnected-(SV2-Pad6)") (class "Default")
      (node (ref "SV2") (pin "6") (pinfunction "6_6") (pintype "passive"))
    )
    (net (code "100") (name "unconnected-(SV2-Pad7)") (class "Default")
      (node (ref "SV2") (pin "7") (pinfunction "7_7") (pintype "passive"))
    )
    (net (code "101") (name "unconnected-(SV2-Pad8)") (class "Default")
      (node (ref "SV2") (pin "8") (pinfunction "8_8") (pintype "passive"))
    )
  )
)
